# receiving_end.net
KiCad netlist of a schematic drawn in EAGLE
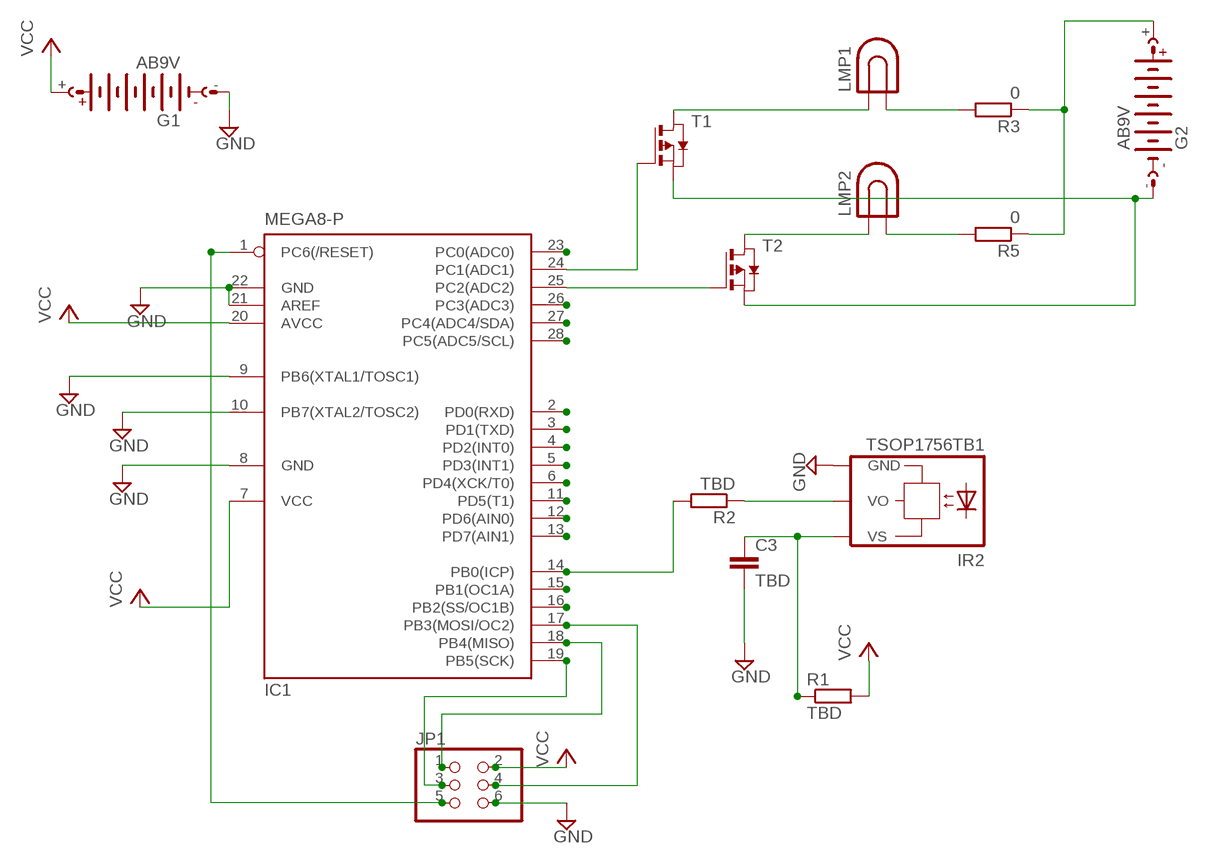
[diagram p0: schematic, sheet 1]

(export (version "E")
  (design (tool "Eeschema 10.0.6"))
  (components
    (comp (ref "C3")
      (value "TBD")
      (footprint "eagle-import:C0805")
      (libsource (lib "eagle-import") (part "C-EUC0805"))
    )
    (comp (ref "G1")
      (value "AB9V")
      (footprint "eagle-import:AB9V")
      (libsource (lib "eagle-import") (part "AB9V"))
    )
    (comp (ref "G2")
      (value "AB9V")
      (footprint "eagle-import:AB9V")
      (libsource (lib "eagle-import") (part "AB9V"))
    )
    (comp (ref "IC1")
      (value "MEGA8-P")
      (footprint "eagle-import:DIL28-3")
      (libsource (lib "eagle-import") (part "MEGA8-P"))
    )
    (comp (ref "IR2")
      (value "TSOP1756TB1")
      (footprint "eagle-import:TSOP17_TB1")
      (libsource (lib "eagle-import") (part "TSOP17TB156"))
    )
    (comp (ref "JP1")
      (value "PINHD-2X3")
      (footprint "eagle-import:2X03")
      (libsource (lib "eagle-import") (part "PINHD-2X3"))
    )
    (comp (ref "LMP1")
      (value "LAMP")
      (footprint "eagle-import:LDH-5R")
      (libsource (lib "eagle-import") (part "LAMP"))
    )
    (comp (ref "LMP2")
      (value "LAMP")
      (footprint "eagle-import:LDH-5R")
      (libsource (lib "eagle-import") (part "LAMP"))
    )
    (comp (ref "R1")
      (value "TBD")
      (footprint "eagle-import:R0805")
      (libsource (lib "eagle-import") (part "R-EU_R0805"))
    )
    (comp (ref "R2")
      (value "TBD")
      (footprint "eagle-import:R0805")
      (libsource (lib "eagle-import") (part "R-EU_R0805"))
    )
    (comp (ref "R3")
      (value "0")
      (footprint "eagle-import:R0805")
      (libsource (lib "eagle-import") (part "R-EU_R0805"))
    )
    (comp (ref "R5")
      (value "0")
      (footprint "eagle-import:R0805")
      (libsource (lib "eagle-import") (part "R-EU_R0805"))
    )
    (comp (ref "T1")
      (value "PMOSSOT23ZXM61P02FTA")
      (footprint "eagle-import:SOT-23")
      (libsource (lib "eagle-import") (part "PMOSSOT23ZXM61P02FTA"))
    )
    (comp (ref "T2")
      (value "PMOSSOT23ZXM61P02FTA")
      (footprint "eagle-import:SOT-23")
      (libsource (lib "eagle-import") (part "PMOSSOT23ZXM61P02FTA"))
    )
  )
  (nets
    (net (code "1") (name "GND") (class "Default")
      (node (ref "C3") (pin "2") (pinfunction "2_2") (pintype "passive"))
      (node (ref "G1") (pin "-") (pinfunction "-_-") (pintype "passive"))
      (node (ref "IC1") (pin "10") (pinfunction "PB7(XTAL2/TOSC2)_10") (pintype "bidirectional"))
      (node (ref "IC1") (pin "21") (pinfunction "AREF_21") (pintype "passive"))
      (node (ref "IC1") (pin "22") (pinfunction "GND_22") (pintype "power_in"))
      (node (ref "IC1") (pin "8") (pinfunction "GND_8") (pintype "power_in"))
      (node (ref "IC1") (pin "9") (pinfunction "PB6(XTAL1/TOSC1)_9") (pintype "bidirectional"))
      (node (ref "IR2") (pin "GND") (pinfunction "GND_GND") (pintype "power_in"))
      (node (ref "JP1") (pin "6") (pinfunction "6_6") (pintype "passive"))
    )
    (net (code "2") (name "Net-(C3-Pad1)") (class "Default")
      (node (ref "C3") (pin "1") (pinfunction "1_1") (pintype "passive"))
      (node (ref "IR2") (pin "VS") (pinfunction "VS_VS") (pintype "power_in"))
      (node (ref "R1") (pin "1") (pinfunction "1_1") (pintype "passive"))
    )
    (net (code "3") (name "Net-(G2-Pad+)") (class "Default")
      (node (ref "G2") (pin "+") (pinfunction "+_+") (pintype "passive"))
      (node (ref "R3") (pin "1") (pinfunction "1_1") (pintype "passive"))
      (node (ref "R5") (pin "1") (pinfunction "1_1") (pintype "passive"))
    )
    (net (code "4") (name "Net-(IC1-PB0(ICP))") (class "Default")
      (node (ref "IC1") (pin "14") (pinfunction "PB0(ICP)_14") (pintype "bidirectional"))
      (node (ref "R2") (pin "2") (pinfunction "2_2") (pintype "passive"))
    )
    (net (code "5") (name "Net-(IC1-PB3(MOSI{slash}OC2))") (class "Default")
      (node (ref "IC1") (pin "17") (pinfunction "PB3(MOSI/OC2)_17") (pintype "bidirectional"))
      (node (ref "JP1") (pin "4") (pinfunction "4_4") (pintype "passive"))
    )
    (net (code "6") (name "Net-(IC1-PB4(MISO))") (class "Default")
      (node (ref "IC1") (pin "18") (pinfunction "PB4(MISO)_18") (pintype "bidirectional"))
      (node (ref "JP1") (pin "1") (pinfunction "1_1") (pintype "passive"))
    )
    (net (code "7") (name "Net-(IC1-PB5(SCK))") (class "Default")
      (node (ref "IC1") (pin "19") (pinfunction "PB5(SCK)_19") (pintype "bidirectional"))
      (node (ref "JP1") (pin "3") (pinfunction "3_3") (pintype "passive"))
    )
    (net (code "8") (name "Net-(IC1-PC1(ADC1))") (class "Default")
      (node (ref "IC1") (pin "24") (pinfunction "PC1(ADC1)_24") (pintype "bidirectional"))
      (node (ref "T1") (pin "3") (pinfunction "G_3") (pintype "passive"))
    )
    (net (code "9") (name "Net-(IC1-PC2(ADC2))") (class "Default")
      (node (ref "IC1") (pin "25") (pinfunction "PC2(ADC2)_25") (pintype "bidirectional"))
      (node (ref "T2") (pin "3") (pinfunction "G_3") (pintype "passive"))
    )
    (net (code "10") (name "Net-(IC1-PC6({slash}RESET))") (class "Default")
      (node (ref "IC1") (pin "1") (pinfunction "PC6(/RESET)_1") (pintype "bidirectional"))
      (node (ref "JP1") (pin "5") (pinfunction "5_5") (pintype "passive"))
    )
    (net (code "11") (name "Net-(IR2-PadVO)") (class "Default")
      (node (ref "IR2") (pin "VO") (pinfunction "VO_VO") (pintype "open_collector"))
      (node (ref "R2") (pin "1") (pinfunction "1_1") (pintype "passive"))
    )
    (net (code "12") (name "Net-(LMP1-Pad2)") (class "Default")
      (node (ref "LMP1") (pin "2") (pinfunction "2_2") (pintype "passive"))
      (node (ref "R3") (pin "2") (pinfunction "2_2") (pintype "passive"))
    )
    (net (code "13") (name "Net-(LMP2-Pad2)") (class "Default")
      (node (ref "LMP2") (pin "2") (pinfunction "2_2") (pintype "passive"))
      (node (ref "R5") (pin "2") (pinfunction "2_2") (pintype "passive"))
    )
    (net (code "14") (name "Net-(T1-D)") (class "Default")
      (node (ref "LMP1") (pin "1") (pinfunction "1_1") (pintype "passive"))
      (node (ref "T1") (pin "1") (pinfunction "D_1") (pintype "passive"))
    )
    (net (code "15") (name "Net-(T1-S)") (class "Default")
      (node (ref "G2") (pin "-") (pinfunction "-_-") (pintype "passive"))
      (node (ref "T1") (pin "2") (pinfunction "S_2") (pintype "passive"))
      (node (ref "T2") (pin "2") (pinfunction "S_2") (pintype "passive"))
    )
    (net (code "16") (name "Net-(T2-D)") (class "Default")
      (node (ref "LMP2") (pin "1") (pinfunction "1_1") (pintype "passive"))
      (node (ref "T2") (pin "1") (pinfunction "D_1") (pintype "passive"))
    )
    (net (code "17") (name "VCC") (class "Default")
      (node (ref "G1") (pin "+") (pinfunction "+_+") (pintype "passive"))
      (node (ref "IC1") (pin "20") (pinfunction "AVCC_20") (pintype "power_in"))
      (node (ref "IC1") (pin "7") (pinfunction "VCC_7") (pintype "power_in"))
      (node (ref "JP1") (pin "2") (pinfunction "2_2") (pintype "passive"))
      (node (ref "R1") (pin "2") (pinfunction "2_2") (pintype "passive"))
    )
    (net (code "18") (name "unconnected-(IC1-PB1(OC1A)-Pad15)") (class "Default")
      (node (ref "IC1") (pin "15") (pinfunction "PB1(OC1A)_15") (pintype "bidirectional"))
    )
    (net (code "19") (name "unconnected-(IC1-PB2(SS{slash}OC1B)-Pad16)") (class "Default")
      (node (ref "IC1") (pin "16") (pinfunction "PB2(SS/OC1B)_16") (pintype "bidirectional"))
    )
    (net (code "20") (name "unconnected-(IC1-PC0(ADC0)-Pad23)") (class "Default")
      (node (ref "IC1") (pin "23") (pinfunction "PC0(ADC0)_23") (pintype "bidirectional"))
    )
    (net (code "21") (name "unconnected-(IC1-PC3(ADC3)-Pad26)") (class "Default")
      (node (ref "IC1") (pin "26") (pinfunction "PC3(ADC3)_26") (pintype "bidirectional"))
    )
    (net (code "22") (name "unconnected-(IC1-PC4(ADC4{slash}SDA)-Pad27)") (class "Default")
      (node (ref "IC1") (pin "27") (pinfunction "PC4(ADC4/SDA)_27") (pintype "bidirectional"))
    )
    (net (code "23") (name "unconnected-(IC1-PC5(ADC5{slash}SCL)-Pad28)") (class "Default")
      (node (ref "IC1") (pin "28") (pinfunction "PC5(ADC5/SCL)_28") (pintype "bidirectional"))
    )
    (net (code "24") (name "unconnected-(IC1-PD0(RXD)-Pad2)") (class "Default")
      (node (ref "IC1") (pin "2") (pinfunction "PD0(RXD)_2") (pintype "bidirectional"))
    )
    (net (code "25") (name "unconnected-(IC1-PD1(TXD)-Pad3)") (class "Default")
      (node (ref "IC1") (pin "3") (pinfunction "PD1(TXD)_3") (pintype "bidirectional"))
    )
    (net (code "26") (name "unconnected-(IC1-PD2(INT0)-Pad4)") (class "Default")
      (node (ref "IC1") (pin "4") (pinfunction "PD2(INT0)_4") (pintype "bidirectional"))
    )
    (net (code "27") (name "unconnected-(IC1-PD3(INT1)-Pad5)") (class "Default")
      (node (ref "IC1") (pin "5") (pinfunction "PD3(INT1)_5") (pintype "bidirectional"))
    )
    (net (code "28") (name "unconnected-(IC1-PD4(XCK{slash}T0)-Pad6)") (class "Default")
      (node (ref "IC1") (pin "6") (pinfunction "PD4(XCK/T0)_6") (pintype "bidirectional"))
    )
    (net (code "29") (name "unconnected-(IC1-PD5(T1)-Pad11)") (class "Default")
      (node (ref "IC1") (pin "11") (pinfunction "PD5(T1)_11") (pintype "bidirectional"))
    )
    (net (code "30") (name "unconnected-(IC1-PD6(AIN0)-Pad12)") (class "Default")
      (node (ref "IC1") (pin "12") (pinfunction "PD6(AIN0)_12") (pintype "bidirectional"))
    )
    (net (code "31") (name "unconnected-(IC1-PD7(AIN1)-Pad13)") (class "Default")
      (node (ref "IC1") (pin "13") (pinfunction "PD7(AIN1)_13") (pintype "bidirectional"))
    )
  )
)
